# Wordclock-back2.net
KiCad netlist of a schematic drawn in EAGLE
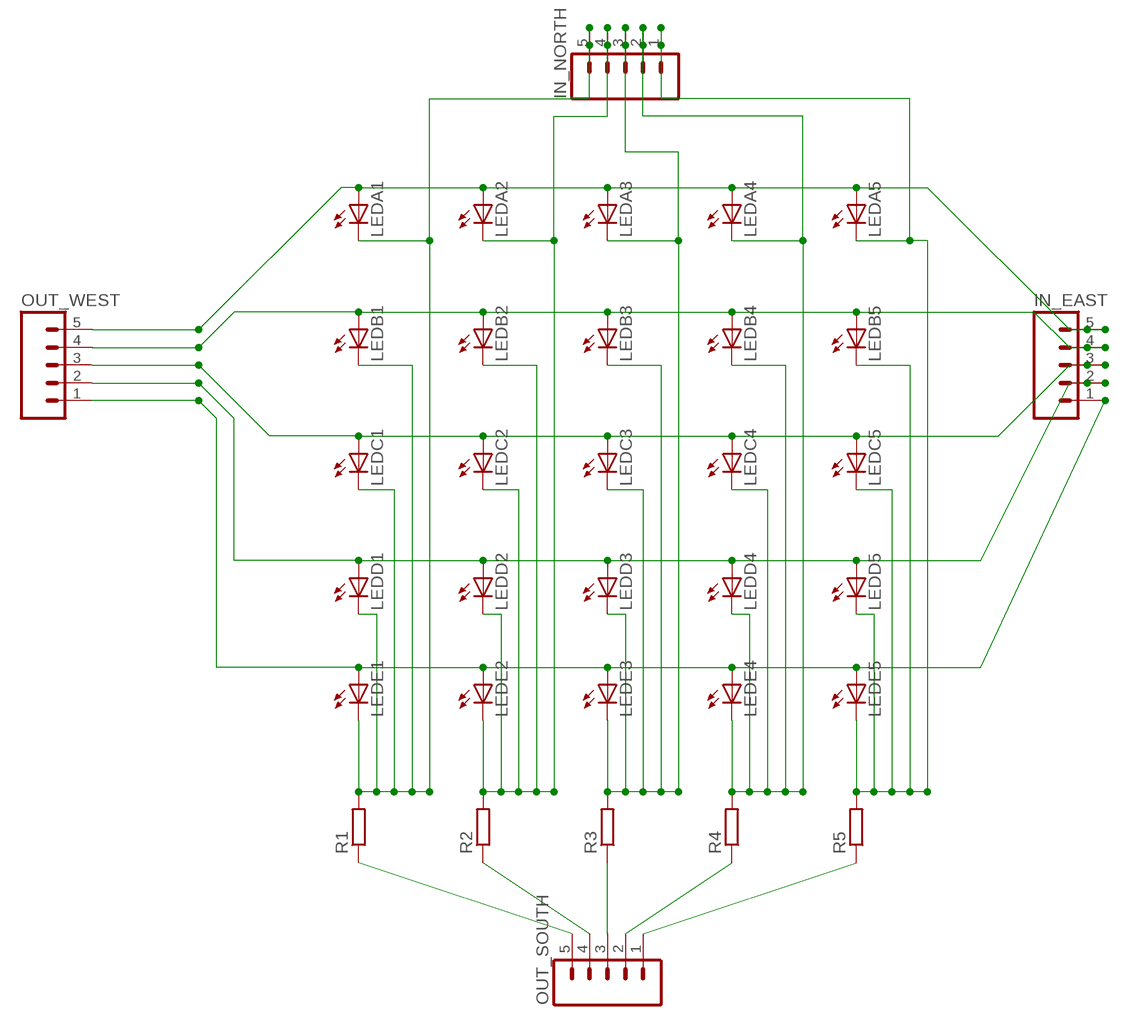
[diagram p0: schematic, sheet 1]

(export (version "E")
  (design (tool "Eeschema 10.0.6"))
  (components
    (comp (ref "IN_EAST")
      (value "M05PTH")
      (footprint "eagle-import:1X05")
      (libsource (lib "eagle-import") (part "M05PTH"))
    )
    (comp (ref "IN_NORTH")
      (value "M05PTH")
      (footprint "eagle-import:1X05")
      (libsource (lib "eagle-import") (part "M05PTH"))
    )
    (comp (ref "LEDA1")
      (value "LED3MM")
      (footprint "eagle-import:LED3MM")
      (libsource (lib "eagle-import") (part "LED3MM"))
    )
    (comp (ref "LEDA2")
      (value "LED3MM")
      (footprint "eagle-import:LED3MM")
      (libsource (lib "eagle-import") (part "LED3MM"))
    )
    (comp (ref "LEDA3")
      (value "LED3MM")
      (footprint "eagle-import:LED3MM")
      (libsource (lib "eagle-import") (part "LED3MM"))
    )
    (comp (ref "LEDA4")
      (value "LED3MM")
      (footprint "eagle-import:LED3MM")
      (libsource (lib "eagle-import") (part "LED3MM"))
    )
    (comp (ref "LEDA5")
      (value "LED3MM")
      (footprint "eagle-import:LED3MM")
      (libsource (lib "eagle-import") (part "LED3MM"))
    )
    (comp (ref "LEDB1")
      (value "LED3MM")
      (footprint "eagle-import:LED3MM")
      (libsource (lib "eagle-import") (part "LED3MM"))
    )
    (comp (ref "LEDB2")
      (value "LED3MM")
      (footprint "eagle-import:LED3MM")
      (libsource (lib "eagle-import") (part "LED3MM"))
    )
    (comp (ref "LEDB3")
      (value "LED3MM")
      (footprint "eagle-import:LED3MM")
      (libsource (lib "eagle-import") (part "LED3MM"))
    )
    (comp (ref "LEDB4")
      (value "LED3MM")
      (footprint "eagle-import:LED3MM")
      (libsource (lib "eagle-import") (part "LED3MM"))
    )
    (comp (ref "LEDB5")
      (value "LED3MM")
      (footprint "eagle-import:LED3MM")
      (libsource (lib "eagle-import") (part "LED3MM"))
    )
    (comp (ref "LEDC1")
      (value "LED3MM")
      (footprint "eagle-import:LED3MM")
      (libsource (lib "eagle-import") (part "LED3MM"))
    )
    (comp (ref "LEDC2")
      (value "LED3MM")
      (footprint "eagle-import:LED3MM")
      (libsource (lib "eagle-import") (part "LED3MM"))
    )
    (comp (ref "LEDC3")
      (value "LED3MM")
      (footprint "eagle-import:LED3MM")
      (libsource (lib "eagle-import") (part "LED3MM"))
    )
    (comp (ref "LEDC4")
      (value "LED3MM")
      (footprint "eagle-import:LED3MM")
      (libsource (lib "eagle-import") (part "LED3MM"))
    )
    (comp (ref "LEDC5")
      (value "LED3MM")
      (footprint "eagle-import:LED3MM")
      (libsource (lib "eagle-import") (part "LED3MM"))
    )
    (comp (ref "LEDD1")
      (value "LED3MM")
      (footprint "eagle-import:LED3MM")
      (libsource (lib "eagle-import") (part "LED3MM"))
    )
    (comp (ref "LEDD2")
      (value "LED3MM")
      (footprint "eagle-import:LED3MM")
      (libsource (lib "eagle-import") (part "LED3MM"))
    )
    (comp (ref "LEDD3")
      (value "LED3MM")
      (footprint "eagle-import:LED3MM")
      (libsource (lib "eagle-import") (part "LED3MM"))
    )
    (comp (ref "LEDD4")
      (value "LED3MM")
      (footprint "eagle-import:LED3MM")
      (libsource (lib "eagle-import") (part "LED3MM"))
    )
    (comp (ref "LEDD5")
      (value "LED3MM")
      (footprint "eagle-import:LED3MM")
      (libsource (lib "eagle-import") (part "LED3MM"))
    )
    (comp (ref "LEDE1")
      (value "LED3MM")
      (footprint "eagle-import:LED3MM")
      (libsource (lib "eagle-import") (part "LED3MM"))
    )
    (comp (ref "LEDE2")
      (value "LED3MM")
      (footprint "eagle-import:LED3MM")
      (libsource (lib "eagle-import") (part "LED3MM"))
    )
    (comp (ref "LEDE3")
      (value "LED3MM")
      (footprint "eagle-import:LED3MM")
      (libsource (lib "eagle-import") (part "LED3MM"))
    )
    (comp (ref "LEDE4")
      (value "LED3MM")
      (footprint "eagle-import:LED3MM")
      (libsource (lib "eagle-import") (part "LED3MM"))
    )
    (comp (ref "LEDE5")
      (value "LED3MM")
      (footprint "eagle-import:LED3MM")
      (libsource (lib "eagle-import") (part "LED3MM"))
    )
    (comp (ref "OUT_SOUTH")
      (value "M05PTH")
      (footprint "eagle-import:1X05")
      (libsource (lib "eagle-import") (part "M05PTH"))
    )
    (comp (ref "OUT_WEST")
      (value "M05PTH")
      (footprint "eagle-import:1X05")
      (libsource (lib "eagle-import") (part "M05PTH"))
    )
    (comp (ref "R1")
      (value "R-EU_0204/7")
      (footprint "eagle-import:0204_7")
      (libsource (lib "eagle-import") (part "R-EU_0204/7"))
    )
    (comp (ref "R2")
      (value "R-EU_0204/7")
      (footprint "eagle-import:0204_7")
      (libsource (lib "eagle-import") (part "R-EU_0204/7"))
    )
    (comp (ref "R3")
      (value "R-EU_0204/7")
      (footprint "eagle-import:0204_7")
      (libsource (lib "eagle-import") (part "R-EU_0204/7"))
    )
    (comp (ref "R4")
      (value "R-EU_0204/7")
      (footprint "eagle-import:0204_7")
      (libsource (lib "eagle-import") (part "R-EU_0204/7"))
    )
    (comp (ref "R5")
      (value "R-EU_0204/7")
      (footprint "eagle-import:0204_7")
      (libsource (lib "eagle-import") (part "R-EU_0204/7"))
    )
  )
  (nets
    (net (code "1") (name "Net-(IN_EAST-Pad1)") (class "Default")
      (node (ref "IN_EAST") (pin "1") (pinfunction "1_1") (pintype "passive"))
      (node (ref "LEDE1") (pin "A") (pinfunction "A_A") (pintype "passive"))
      (node (ref "LEDE2") (pin "A") (pinfunction "A_A") (pintype "passive"))
      (node (ref "LEDE3") (pin "A") (pinfunction "A_A") (pintype "passive"))
      (node (ref "LEDE4") (pin "A") (pinfunction "A_A") (pintype "passive"))
      (node (ref "LEDE5") (pin "A") (pinfunction "A_A") (pintype "passive"))
      (node (ref "OUT_WEST") (pin "1") (pinfunction "1_1") (pintype "passive"))
    )
    (net (code "2") (name "Net-(IN_EAST-Pad2)") (class "Default")
      (node (ref "IN_EAST") (pin "2") (pinfunction "2_2") (pintype "passive"))
      (node (ref "LEDD1") (pin "A") (pinfunction "A_A") (pintype "passive"))
      (node (ref "LEDD2") (pin "A") (pinfunction "A_A") (pintype "passive"))
      (node (ref "LEDD3") (pin "A") (pinfunction "A_A") (pintype "passive"))
      (node (ref "LEDD4") (pin "A") (pinfunction "A_A") (pintype "passive"))
      (node (ref "LEDD5") (pin "A") (pinfunction "A_A") (pintype "passive"))
      (node (ref "OUT_WEST") (pin "2") (pinfunction "2_2") (pintype "passive"))
    )
    (net (code "3") (name "Net-(IN_EAST-Pad3)") (class "Default")
      (node (ref "IN_EAST") (pin "3") (pinfunction "3_3") (pintype "passive"))
      (node (ref "LEDC1") (pin "A") (pinfunction "A_A") (pintype "passive"))
      (node (ref "LEDC2") (pin "A") (pinfunction "A_A") (pintype "passive"))
      (node (ref "LEDC3") (pin "A") (pinfunction "A_A") (pintype "passive"))
      (node (ref "LEDC4") (pin "A") (pinfunction "A_A") (pintype "passive"))
      (node (ref "LEDC5") (pin "A") (pinfunction "A_A") (pintype "passive"))
      (node (ref "OUT_WEST") (pin "3") (pinfunction "3_3") (pintype "passive"))
    )
    (net (code "4") (name "Net-(IN_EAST-Pad4)") (class "Default")
      (node (ref "IN_EAST") (pin "4") (pinfunction "4_4") (pintype "passive"))
      (node (ref "LEDB1") (pin "A") (pinfunction "A_A") (pintype "passive"))
      (node (ref "LEDB2") (pin "A") (pinfunction "A_A") (pintype "passive"))
      (node (ref "LEDB3") (pin "A") (pinfunction "A_A") (pintype "passive"))
      (node (ref "LEDB4") (pin "A") (pinfunction "A_A") (pintype "passive"))
      (node (ref "LEDB5") (pin "A") (pinfunction "A_A") (pintype "passive"))
      (node (ref "OUT_WEST") (pin "4") (pinfunction "4_4") (pintype "passive"))
    )
    (net (code "5") (name "Net-(IN_EAST-Pad5)") (class "Default")
      (node (ref "IN_EAST") (pin "5") (pinfunction "5_5") (pintype "passive"))
      (node (ref "LEDA1") (pin "A") (pinfunction "A_A") (pintype "passive"))
      (node (ref "LEDA2") (pin "A") (pinfunction "A_A") (pintype "passive"))
      (node (ref "LEDA3") (pin "A") (pinfunction "A_A") (pintype "passive"))
      (node (ref "LEDA4") (pin "A") (pinfunction "A_A") (pintype "passive"))
      (node (ref "LEDA5") (pin "A") (pinfunction "A_A") (pintype "passive"))
      (node (ref "OUT_WEST") (pin "5") (pinfunction "5_5") (pintype "passive"))
    )
    (net (code "6") (name "Net-(LEDA1-C)") (class "Default")
      (node (ref "IN_NORTH") (pin "5") (pinfunction "5_5") (pintype "passive"))
      (node (ref "LEDA1") (pin "K") (pinfunction "C_K") (pintype "passive"))
      (node (ref "LEDB1") (pin "K") (pinfunction "C_K") (pintype "passive"))
      (node (ref "LEDC1") (pin "K") (pinfunction "C_K") (pintype "passive"))
      (node (ref "LEDD1") (pin "K") (pinfunction "C_K") (pintype "passive"))
      (node (ref "LEDE1") (pin "K") (pinfunction "C_K") (pintype "passive"))
      (node (ref "R1") (pin "2") (pinfunction "2_2") (pintype "passive"))
    )
    (net (code "7") (name "Net-(LEDA2-C)") (class "Default")
      (node (ref "IN_NORTH") (pin "4") (pinfunction "4_4") (pintype "passive"))
      (node (ref "LEDA2") (pin "K") (pinfunction "C_K") (pintype "passive"))
      (node (ref "LEDB2") (pin "K") (pinfunction "C_K") (pintype "passive"))
      (node (ref "LEDC2") (pin "K") (pinfunction "C_K") (pintype "passive"))
      (node (ref "LEDD2") (pin "K") (pinfunction "C_K") (pintype "passive"))
      (node (ref "LEDE2") (pin "K") (pinfunction "C_K") (pintype "passive"))
      (node (ref "R2") (pin "2") (pinfunction "2_2") (pintype "passive"))
    )
    (net (code "8") (name "Net-(LEDA3-C)") (class "Default")
      (node (ref "IN_NORTH") (pin "3") (pinfunction "3_3") (pintype "passive"))
      (node (ref "LEDA3") (pin "K") (pinfunction "C_K") (pintype "passive"))
      (node (ref "LEDB3") (pin "K") (pinfunction "C_K") (pintype "passive"))
      (node (ref "LEDC3") (pin "K") (pinfunction "C_K") (pintype "passive"))
      (node (ref "LEDD3") (pin "K") (pinfunction "C_K") (pintype "passive"))
      (node (ref "LEDE3") (pin "K") (pinfunction "C_K") (pintype "passive"))
      (node (ref "R3") (pin "2") (pinfunction "2_2") (pintype "passive"))
    )
    (net (code "9") (name "Net-(LEDA4-C)") (class "Default")
      (node (ref "IN_NORTH") (pin "2") (pinfunction "2_2") (pintype "passive"))
      (node (ref "LEDA4") (pin "K") (pinfunction "C_K") (pintype "passive"))
      (node (ref "LEDB4") (pin "K") (pinfunction "C_K") (pintype "passive"))
      (node (ref "LEDC4") (pin "K") (pinfunction "C_K") (pintype "passive"))
      (node (ref "LEDD4") (pin "K") (pinfunction "C_K") (pintype "passive"))
      (node (ref "LEDE4") (pin "K") (pinfunction "C_K") (pintype "passive"))
      (node (ref "R4") (pin "2") (pinfunction "2_2") (pintype "passive"))
    )
    (net (code "10") (name "Net-(LEDA5-C)") (class "Default")
      (node (ref "IN_NORTH") (pin "1") (pinfunction "1_1") (pintype "passive"))
      (node (ref "LEDA5") (pin "K") (pinfunction "C_K") (pintype "passive"))
      (node (ref "LEDB5") (pin "K") (pinfunction "C_K") (pintype "passive"))
      (node (ref "LEDC5") (pin "K") (pinfunction "C_K") (pintype "passive"))
      (node (ref "LEDD5") (pin "K") (pinfunction "C_K") (pintype "passive"))
      (node (ref "LEDE5") (pin "K") (pinfunction "C_K") (pintype "passive"))
      (node (ref "R5") (pin "2") (pinfunction "2_2") (pintype "passive"))
    )
    (net (code "11") (name "Net-(OUT_SOUTH-Pad1)") (class "Default")
      (node (ref "OUT_SOUTH") (pin "1") (pinfunction "1_1") (pintype "passive"))
      (node (ref "R5") (pin "1") (pinfunction "1_1") (pintype "passive"))
    )
    (net (code "12") (name "Net-(OUT_SOUTH-Pad2)") (class "Default")
      (node (ref "OUT_SOUTH") (pin "2") (pinfunction "2_2") (pintype "passive"))
      (node (ref "R4") (pin "1") (pinfunction "1_1") (pintype "passive"))
    )
    (net (code "13") (name "Net-(OUT_SOUTH-Pad3)") (class "Default")
      (node (ref "OUT_SOUTH") (pin "3") (pinfunction "3_3") (pintype "passive"))
      (node (ref "R3") (pin "1") (pinfunction "1_1") (pintype "passive"))
    )
    (net (code "14") (name "Net-(OUT_SOUTH-Pad4)") (class "Default")
      (node (ref "OUT_SOUTH") (pin "4") (pinfunction "4_4") (pintype "passive"))
      (node (ref "R2") (pin "1") (pinfunction "1_1") (pintype "passive"))
    )
    (net (code "15") (name "Net-(OUT_SOUTH-Pad5)") (class "Default")
      (node (ref "OUT_SOUTH") (pin "5") (pinfunction "5_5") (pintype "passive"))
      (node (ref "R1") (pin "1") (pinfunction "1_1") (pintype "passive"))
    )
  )
)
